# TPS61169_SEPIC_90_mA_LED_Driver.net
KiCad netlist of a schematic drawn in Altium Designer
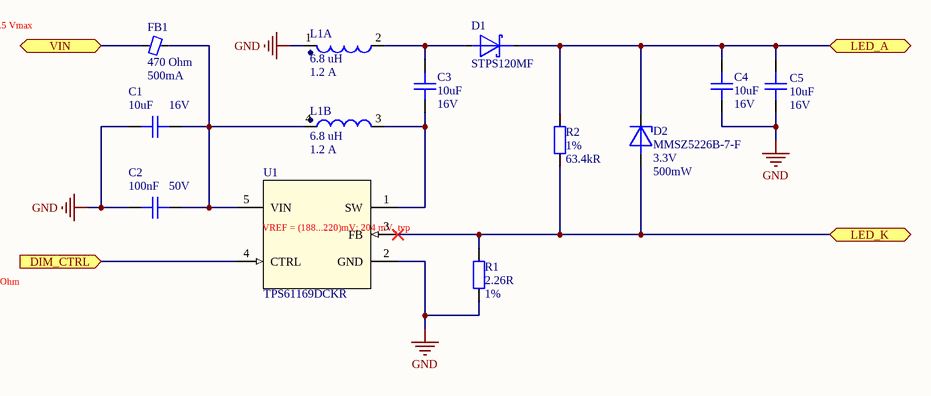
[diagram p0: TPS61169_SEPIC_90_mA_LED_Driver.SchDoc]

(export (version "E")
  (design (tool "Eeschema 10.0.6"))
  (components
    (comp (ref "C1")
      (value "CAP CER 10UF 16V X5R 0603")
      (footprint "C0603")
      (description "10µF ±10% 16V Ceramic Capacitor X5R 0603 (1608 Metric)")
      (fields
        (field (name "MANUFACTURER") "Murata")
        (field (name "MANUFACTURER PART NUMBER") "GRM188R61C106KAALJ")
        (field (name "VOLTAGE RATING") "16V")
        (field (name "CAPACITANCE") "10uF")
      )
      (libsource (lib "capacitors_smd") (part "CAP CER 10UF 16V X5R 0603"))
    )
    (comp (ref "C2")
      (value "CAP CER 0.1UF 50V X7R 0402")
      (footprint "C0402")
      (description "0.1µF ±10% 50V Ceramic Capacitor X7R 0402 (1005 Metric)")
      (fields
        (field (name "MANUFACTURER") "TDK")
        (field (name "MANUFACTURER PART NUMBER") "CGA2B3X7R1H104K050BB")
        (field (name "CAPACITANCE") "100nF")
        (field (name "VOLTAGE") "50V")
      )
      (libsource (lib "capacitors_smd") (part "CAP CER 0.1UF 50V X7R 0402"))
    )
    (comp (ref "C3")
      (value "CAP CER 10UF 16V X7R 0805")
      (footprint "C0805")
      (description "10µF ±10% 16V Ceramic Capacitor X7R 0805 (2012 Metric)")
      (fields
        (field (name "MANUFACTURER") "Samsung")
        (field (name "MANUFACTURER PART NUMBER") "CL21B106KOQNNNG")
        (field (name "CAPACITANCE") "10uF")
        (field (name "VOLTAGE RATING") "16V")
      )
      (libsource (lib "capacitors_smd") (part "CAP CER 10UF 16V X7R 0805"))
    )
    (comp (ref "C4")
      (value "CAP CER 10UF 16V X5R 0603")
      (footprint "C0603")
      (description "10µF ±10% 16V Ceramic Capacitor X5R 0603 (1608 Metric)")
      (fields
        (field (name "MANUFACTURER") "Murata")
        (field (name "MANUFACTURER PART NUMBER") "GRM188R61C106KAALJ")
        (field (name "CAPACITANCE") "10uF")
        (field (name "VOLTAGE RATING") "16V")
      )
      (libsource (lib "capacitors_smd") (part "CAP CER 10UF 16V X5R 0603"))
    )
    (comp (ref "C5")
      (value "CAP CER 10UF 16V X5R 0603")
      (footprint "C0603")
      (description "10µF ±10% 16V Ceramic Capacitor X5R 0603 (1608 Metric)")
      (fields
        (field (name "MANUFACTURER") "Murata")
        (field (name "MANUFACTURER PART NUMBER") "GRM188R61C106KAALJ")
        (field (name "VOLTAGE RATING") "16V")
        (field (name "CAPACITANCE") "10uF")
      )
      (libsource (lib "capacitors_smd") (part "CAP CER 10UF 16V X5R 0603"))
    )
    (comp (ref "D1")
      (value "STPS120MF")
      (footprint "SODFL375X95-2N")
      (description "Diode Schottky 20V 1A Surface Mount STmite Flat")
      (fields (field (name "MANUFACTURER") "STMicroelectronics"))
      (libsource (lib "diodes_schottky") (part "DIODE SCHOTTKY 20V 1A STMITEFLAT"))
    )
    (comp (ref "D2")
      (value "MMSZ5226B-7-F")
      (footprint "SOD-123")
      (description "Zener Diode ±5% Surface Mount SOD-123")
      (fields
        (field (name "MANUFACTURER") "Diodes")
        (field (name "TOLERANCE") "5%")
        (field (name "WORKING VOLTAGE") "3.3V")
        (field (name "POWER RATING") "500mW")
      )
      (libsource (lib "diodes_zener") (part "DIODE ZENER 3.3V 500MW SOD123"))
    )
    (comp (ref "FB1")
      (value "FERRITE BEAD 470 OHM 0603 1LN")
      (footprint "L0603")
      (description "470 Ohms @ 100MHz 1  Ferrite Bead 0603 (1608 Metric) 500mA 210mOhm")
      (fields
        (field (name "MANUFACTURER") "Murata")
        (field (name "MANUFACTURER PART NUMBER") "BLM18EG471SN1D")
        (field (name "IMPEDANCE") "470 Ohm")
        (field (name "CURRENT RATING") "500mA")
      )
      (libsource (lib "ferrite_beads") (part "FERRITE BEAD 470 OHM 0603 1LN"))
    )
    (comp (ref "L1")
      (value "FIXED IND COUIPLED 6.8UH 1.2A 160 mOHM SMD")
      (footprint "IND_LPD5030")
      (description "6.8µH Shielded Coupled Inductors 1.2A 160mOhm Max 1919 (4.8x4.8 Metric)")
      (fields
        (field (name "MANUFACTURER") "Coilcraft")
        (field (name "MANUFACTURER PART NUMBER") "LPD5030-682MR")
        (field (name "INDUCTANCE") "6.8 uH")
        (field (name "MAXIMUM DC CURRENT") "1.2 A")
      )
      (libsource (lib "inductors_smd") (part "FIXED IND COUIPLED 6.8UH 1.2A 160 mOHM SMD"))
    )
    (comp (ref "R1")
      (value "RES SMD 2.26 OHM 1% 1/10W 0603")
      (footprint "R0603")
      (description "2.26 Ohms ±1% 0.1W, 1/10W Chip Resistor 0603 (1608 Metric) Automotive AEC-Q200 Thick Film")
      (fields
        (field (name "MANUFACTURER PART NUMBER") "CRCW06032R26FKEA")
        (field (name "MANUFACTURER") "Vishay Dale")
        (field (name "RESISTANCE") "2.26R")
        (field (name "TOLERANCE") "1%")
      )
      (libsource (lib "resistors_smd") (part "RES SMD 2.26 OHM 1% 1/10W 0603"))
    )
    (comp (ref "R2")
      (value "RES SMD 63.4K OHM 1% 1/16W 0402")
      (footprint "R0402")
      (description "63.4 kOhms ±1% 0.063W, 1/16W Chip Resistor 0402 (1005 Metric) Moisture Resistant Thick Film")
      (fields
        (field (name "MANUFACTURER") "Yageo")
        (field (name "MANUFACTURER PART NUMBER") "RC0402FR-0763K4L")
        (field (name "TOLERANCE") "1%")
        (field (name "RESISTANCE") "63.4kR")
      )
      (libsource (lib "resistors_smd") (part "RES SMD 63.4K OHM 1% 1/16W 0402"))
    )
    (comp (ref "U1")
      (value "TPS61169DCKR")
      (footprint "DCK0005A_L")
      (description "LED Driver IC 1 Output DC DC Regulator Step-Up (Boost) PWM Dimming 1.8A (Switch) SC-70-5")
      (fields (field (name "MANUFACTURER") "Texas Instruments"))
      (libsource (lib "dcdc_converters") (part "IC TPS61169 WLED BACKLIGHT DRIVER SC70-5"))
    )
  )
  (nets
    (net (code "1") (name "/DIM_CTRL") (class "Default")
      (node (ref "U1") (pin "4") (pinfunction "CTRL_4") (pintype "input"))
    )
    (net (code "2") (name "/LED_A") (class "Default")
      (node (ref "C4") (pin "2") (pinfunction "2_2") (pintype "passive"))
      (node (ref "C5") (pin "1") (pinfunction "1_1") (pintype "passive"))
      (node (ref "D1") (pin "1") (pinfunction "K_1") (pintype "passive"))
      (node (ref "D2") (pin "1") (pinfunction "K_1") (pintype "passive"))
      (node (ref "R2") (pin "1") (pinfunction "1_1") (pintype "passive"))
    )
    (net (code "3") (name "/LED_K") (class "Default")
      (node (ref "D2") (pin "2") (pinfunction "A_2") (pintype "passive"))
      (node (ref "R1") (pin "2") (pinfunction "2_2") (pintype "passive"))
      (node (ref "R2") (pin "2") (pinfunction "2_2") (pintype "passive"))
      (node (ref "U1") (pin "3") (pinfunction "FB_3") (pintype "input"))
    )
    (net (code "4") (name "/VIN") (class "Default")
      (node (ref "FB1") (pin "1") (pinfunction "1_1") (pintype "passive"))
    )
    (net (code "5") (name "GND") (class "Default")
      (node (ref "C1") (pin "1") (pinfunction "1_1") (pintype "passive"))
      (node (ref "C2") (pin "2") (pinfunction "2_2") (pintype "passive"))
      (node (ref "C4") (pin "1") (pinfunction "1_1") (pintype "passive"))
      (node (ref "C5") (pin "2") (pinfunction "2_2") (pintype "passive"))
      (node (ref "L1") (pin "1") (pinfunction "1_1") (pintype "passive"))
      (node (ref "R1") (pin "1") (pinfunction "1_1") (pintype "passive"))
      (node (ref "U1") (pin "2") (pinfunction "GND_2") (pintype "power_in"))
    )
    (net (code "6") (name "Net-(D1-A)") (class "Default")
      (node (ref "C3") (pin "2") (pinfunction "2_2") (pintype "passive"))
      (node (ref "D1") (pin "2") (pinfunction "A_2") (pintype "passive"))
      (node (ref "L1") (pin "2") (pinfunction "2_2") (pintype "passive"))
    )
    (net (code "7") (name "Net-(U1-SW)") (class "Default")
      (node (ref "C3") (pin "1") (pinfunction "1_1") (pintype "passive"))
      (node (ref "L1") (pin "3") (pinfunction "3_3") (pintype "passive"))
      (node (ref "U1") (pin "1") (pinfunction "SW_1") (pintype "power_in"))
    )
    (net (code "8") (name "Net-(U1-VIN)") (class "Default")
      (node (ref "C1") (pin "2") (pinfunction "2_2") (pintype "passive"))
      (node (ref "C2") (pin "1") (pinfunction "1_1") (pintype "passive"))
      (node (ref "FB1") (pin "2") (pinfunction "2_2") (pintype "passive"))
      (node (ref "L1") (pin "4") (pinfunction "4_4") (pintype "passive"))
      (node (ref "U1") (pin "5") (pinfunction "VIN_5") (pintype "power_in"))
    )
  )
)
